# 03_USB.net
KiCad netlist of a schematic drawn in Altium Designer
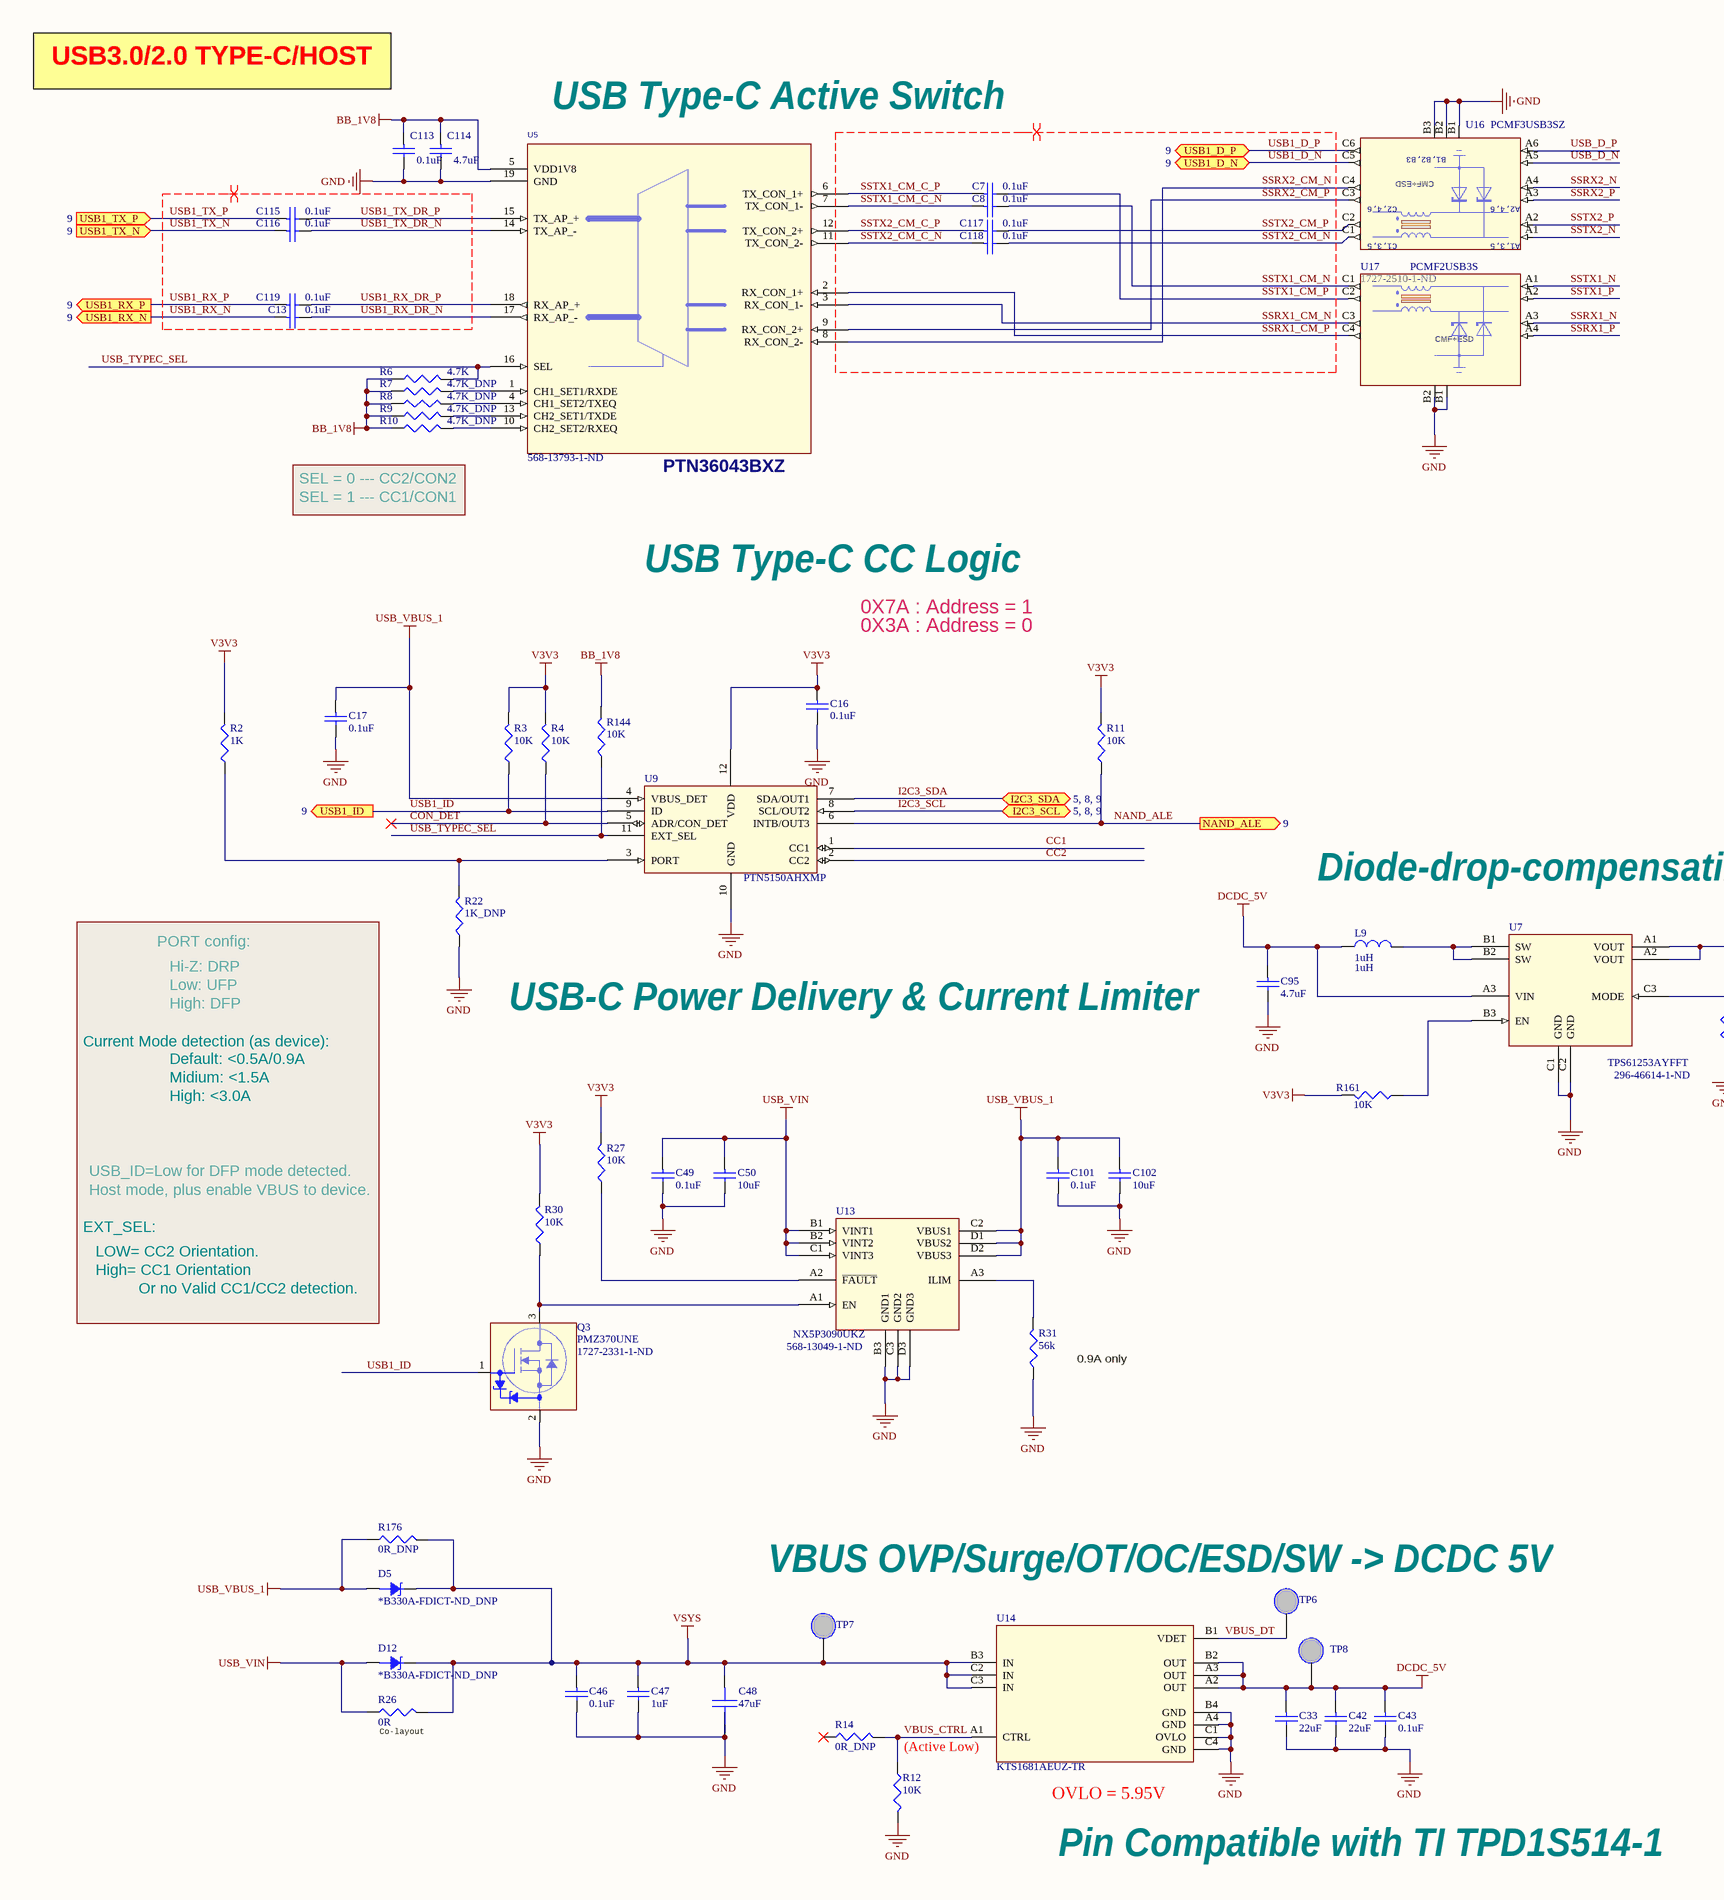
[diagram p0: 03_USB.SchDoc, left]
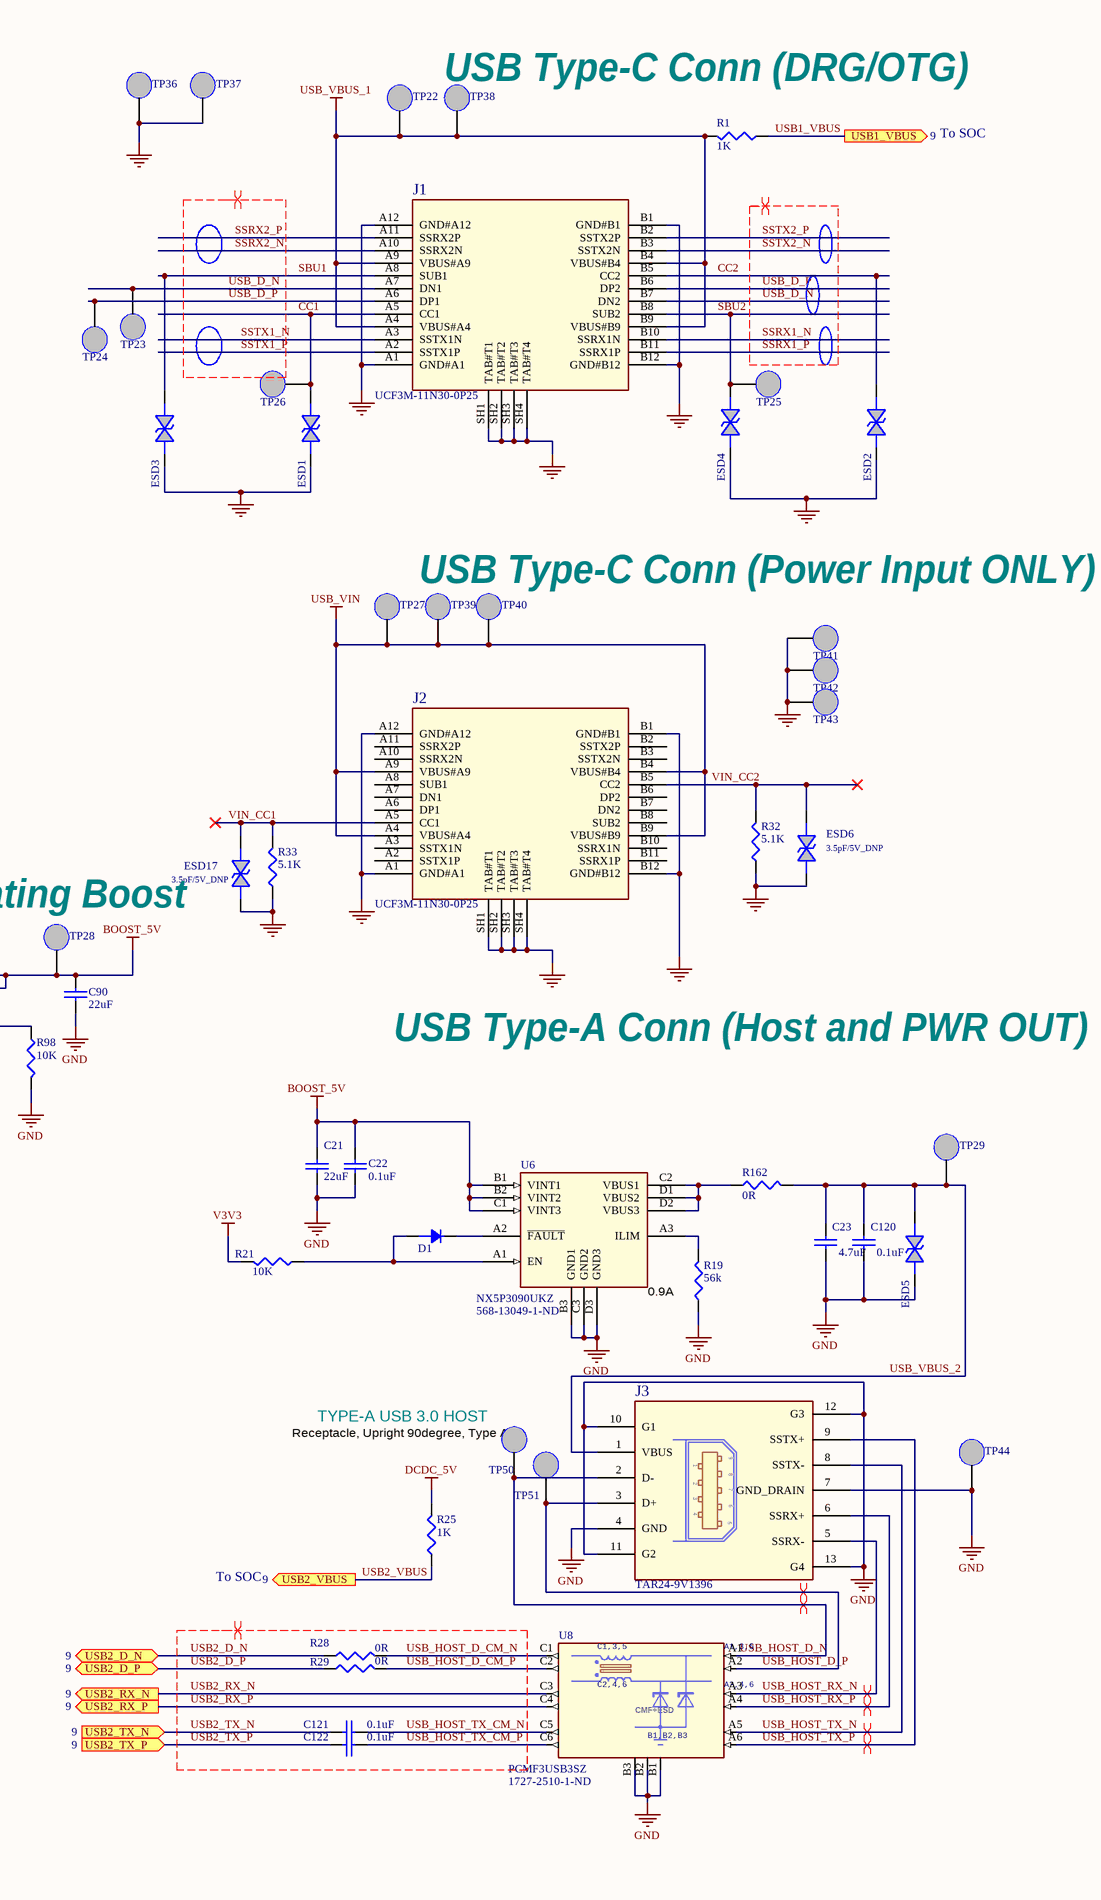
[diagram p1: 03_USB.SchDoc, right]

(export (version "E")
  (design (tool "Eeschema 10.0.6"))
  (components
    (comp (ref "C7")
      (value "0.1uF")
      (footprint "0201")
      (description "CAP CER 0.1UF 10V 10% X5R 0201")
      (fields (field (name "MPN") "C0603X5R1A104K030BC") (field (name "Comment") "0.1uF/10V"))
      (libsource (lib "links") (part "CAP_0201_0.1uF"))
    )
    (comp (ref "C8")
      (value "0.1uF")
      (footprint "0201")
      (description "CAP CER 0.1UF 10V 10% X5R 0201")
      (fields (field (name "MPN") "C0603X5R1A104K030BC") (field (name "Comment") "0.1uF/10V"))
      (libsource (lib "links") (part "CAP_0201_0.1uF"))
    )
    (comp (ref "C13")
      (value "0.1uF")
      (footprint "0201")
      (description "CAP CER 0.1UF 10V 10% X5R 0201")
      (fields (field (name "MPN") "C0603X5R1A104K030BC") (field (name "Comment") "0.1uF/10V"))
      (libsource (lib "links") (part "CAP_0201_0.1uF"))
    )
    (comp (ref "C16")
      (value "0.1uF")
      (footprint "0402")
      (description "CAP CER 0.1uF 25V 10% X7R 0402")
      (fields (field (name "MPN") "TMK105BJ104KV-F") (field (name "Comment") "0.1uF/25V"))
      (libsource (lib "links") (part "CAP_0402_0.1uF_25V"))
    )
    (comp (ref "C17")
      (value "0.1uF")
      (footprint "0402")
      (description "CAP CER 0.1uF 25V 10% X7R 0402")
      (fields (field (name "MPN") "TMK105BJ104KV-F") (field (name "Comment") "0.1uF/25V"))
      (libsource (lib "links") (part "CAP_0402_0.1uF_25V"))
    )
    (comp (ref "C21")
      (value "22uF")
      (footprint "0603")
      (description "CAP CER 22UF 6.3V 10% X5R 0603")
      (fields (field (name "MPN") "CL10A226KQ8NRNE") (field (name "Comment") "22uF/10V"))
      (libsource (lib "links") (part "CAP_0603_22uF"))
    )
    (comp (ref "C22")
      (value "0.1uF")
      (footprint "0201")
      (description "CAP CER 0.1UF 10V 10% X5R 0201")
      (fields (field (name "MPN") "C0603X5R1A104K030BC") (field (name "Comment") "0.1uF/10V"))
      (libsource (lib "links") (part "CAP_0201_0.1uF"))
    )
    (comp (ref "C23")
      (value "4.7uF")
      (footprint "0603")
      (description "CAP CER 4.7uF 10V 10% X5R 0603")
      (fields (field (name "MPN") "CGB3B1X5R1A475K055AC") (field (name "Comment") "4.7uF/10V"))
      (libsource (lib "links") (part "CAP_0603_4.7uF"))
    )
    (comp (ref "C33")
      (value "22uF")
      (footprint "0603")
      (description "CAP CER 22UF 6.3V 10% X5R 0603")
      (fields (field (name "MPN") "CL10A226KQ8NRNE") (field (name "Comment") "22uF/10V"))
      (libsource (lib "links") (part "CAP_0603_22uF"))
    )
    (comp (ref "C42")
      (value "22uF")
      (footprint "0603")
      (description "CAP CER 22UF 6.3V 10% X5R 0603")
      (fields (field (name "MPN") "CL10A226KQ8NRNE") (field (name "Comment") "22uF/10V"))
      (libsource (lib "links") (part "CAP_0603_22uF"))
    )
    (comp (ref "C43")
      (value "0.1uF")
      (footprint "0201")
      (description "CAP CER 0.1UF 10V 10% X5R 0201")
      (fields (field (name "MPN") "C0603X5R1A104K030BC") (field (name "Comment") "0.1uF/10V"))
      (libsource (lib "links") (part "CAP_0201_0.1uF"))
    )
    (comp (ref "C46")
      (value "0.1uF")
      (footprint "0402")
      (description "CAP CER 0.1uF 25V 10% X7R 0402")
      (fields (field (name "MPN") "TMK105BJ104KV-F") (field (name "Comment") "0.1uF/25V"))
      (libsource (lib "links") (part "CAP_0402_0.1uF_25V"))
    )
    (comp (ref "C47")
      (value "1uF")
      (footprint "0402")
      (description "CAP CER 1.0UF 25V 10% X5R 0402")
      (fields (field (name "MPN") "TMK105BJ105MV-F") (field (name "Comment") "1uF/25V"))
      (libsource (lib "links") (part "CAP_0402_1.0uF_25V"))
    )
    (comp (ref "C48")
      (value "47uF")
      (footprint "1206")
      (description "CAP CER 47UF 25V 20% 1206")
      (fields (field (name "MPN") "C3216JB1E476M160AC") (field (name "Comment") "47uF/25V"))
      (libsource (lib "links") (part "CAP_1206_47uF_25V"))
    )
    (comp (ref "C49")
      (value "0.1uF")
      (footprint "0402")
      (description "CAP CER 0.1uF 25V 10% X7R 0402")
      (fields (field (name "MPN") "TMK105BJ104KV-F") (field (name "Comment") "0.1uF/25V"))
      (libsource (lib "links") (part "CAP_0402_0.1uF_25V"))
    )
    (comp (ref "C50")
      (value "10uF")
      (footprint "0402")
      (description "CAP CER 10UF 10V 20% X5R 0402")
      (fields (field (name "MPN") "CL05A106MP5NUNC") (field (name "Comment") "10uF/10V"))
      (libsource (lib "links") (part "CAP_0603_4.7uF_35V"))
    )
    (comp (ref "C90")
      (value "22uF")
      (footprint "0603")
      (description "CAP CER 22UF 6.3V 10% X5R 0603")
      (fields (field (name "MPN") "CL10A226KQ8NRNE") (field (name "Comment") "10uF/10V"))
      (libsource (lib "links") (part "CAP_0603_22uF"))
    )
    (comp (ref "C95")
      (value "4.7uF")
      (footprint "0603")
      (description "CAP CER 4.7uF 10V 10% X5R 0603")
      (fields (field (name "MPN") "CGB3B1X5R1A475K055AC") (field (name "Comment") "4.7uF/10V"))
      (libsource (lib "links") (part "CAP_0603_4.7uF"))
    )
    (comp (ref "C101")
      (value "0.1uF")
      (footprint "0402")
      (description "CAP CER 0.1uF 25V 10% X7R 0402")
      (fields (field (name "MPN") "TMK105BJ104KV-F") (field (name "Comment") "0.1uF/25V"))
      (libsource (lib "links") (part "CAP_0402_0.1uF_25V"))
    )
    (comp (ref "C102")
      (value "10uF")
      (footprint "0402")
      (description "CAP CER 10UF 10V 20% X5R 0402")
      (fields (field (name "MPN") "CL05A106MP5NUNC") (field (name "Comment") "10uF/10V"))
      (libsource (lib "links") (part "CAP_0603_4.7uF_35V"))
    )
    (comp (ref "C113")
      (value "0.1uF")
      (footprint "0201")
      (description "CAP CER 0.1UF 10V 10% X5R 0201")
      (fields (field (name "MPN") "C0603X5R1A104K030BC") (field (name "Comment") "0.1uF/10V"))
      (libsource (lib "links") (part "CAP_0201_0.1uF"))
    )
    (comp (ref "C114")
      (value "4.7uF")
      (footprint "0402")
      (description "CAP CER 4.7UF 10V 20% X5R 0402")
      (fields (field (name "MPN") "C1005X5R1A475M050BC") (field (name "Comment") "4.7uF/10V"))
      (libsource (lib "links") (part "CAP_0402_4.7uF"))
    )
    (comp (ref "C115")
      (value "0.1uF")
      (footprint "0201")
      (description "CAP CER 0.1UF 10V 10% X5R 0201")
      (fields (field (name "MPN") "C0603X5R1A104K030BC") (field (name "Comment") "0.1uF/10V"))
      (libsource (lib "links") (part "CAP_0201_0.1uF"))
    )
    (comp (ref "C116")
      (value "0.1uF")
      (footprint "0201")
      (description "CAP CER 0.1UF 10V 10% X5R 0201")
      (fields (field (name "MPN") "C0603X5R1A104K030BC") (field (name "Comment") "0.1uF/10V"))
      (libsource (lib "links") (part "CAP_0201_0.1uF"))
    )
    (comp (ref "C117")
      (value "0.1uF")
      (footprint "0201")
      (description "CAP CER 0.1UF 10V 10% X5R 0201")
      (fields (field (name "MPN") "C0603X5R1A104K030BC") (field (name "Comment") "0.1uF/10V"))
      (libsource (lib "links") (part "CAP_0201_0.1uF"))
    )
    (comp (ref "C118")
      (value "0.1uF")
      (footprint "0201")
      (description "CAP CER 0.1UF 10V 10% X5R 0201")
      (fields (field (name "MPN") "C0603X5R1A104K030BC") (field (name "Comment") "0.1uF/10V"))
      (libsource (lib "links") (part "CAP_0201_0.1uF"))
    )
    (comp (ref "C119")
      (value "0.1uF")
      (footprint "0201")
      (description "CAP CER 0.1UF 10V 10% X5R 0201")
      (fields (field (name "MPN") "C0603X5R1A104K030BC") (field (name "Comment") "0.1uF/10V"))
      (libsource (lib "links") (part "CAP_0201_0.1uF"))
    )
    (comp (ref "C120")
      (value "0.1uF")
      (footprint "0201")
      (description "CAP CER 0.1UF 10V 10% X5R 0201")
      (fields (field (name "MPN") "C0603X5R1A104K030BC") (field (name "Comment") "0.1uF/10V"))
      (libsource (lib "links") (part "CAP_0201_0.1uF"))
    )
    (comp (ref "C121")
      (value "0.1uF")
      (footprint "0201")
      (description "CAP CER 0.1UF 10V 10% X5R 0201")
      (fields (field (name "MPN") "C0603X5R1A104K030BC") (field (name "Comment") "0.1uF/10V"))
      (libsource (lib "links") (part "CAP_0201_0.1uF"))
    )
    (comp (ref "C122")
      (value "0.1uF")
      (footprint "0201")
      (description "CAP CER 0.1UF 10V 10% X5R 0201")
      (fields (field (name "MPN") "C0603X5R1A104K030BC") (field (name "Comment") "0.1uF/10V"))
      (libsource (lib "links") (part "CAP_0201_0.1uF"))
    )
    (comp (ref "D1")
      (value "CUS10F30")
      (footprint "0805-Diode")
      (description "DIODE SCHOTTKY 20V 1A 0805")
      (libsource (lib "SpacePark") (part "Diode_Schottky_0805"))
    )
    (comp (ref "D5")
      (value "B330A-FDICT-ND_DNP")
      (footprint "SMA-Diode")
      (description "Diode_Schottky_B330A-13-F")
      (fields
        (field (name "SUPPLIER PART NUMBER 1") "*B330A-FDICT-ND_DNP")
        (field (name "MPN") "B330A-FDICT-ND")
      )
      (libsource (lib "SpacePark") (part "B330A-FDICT-ND_DNP"))
    )
    (comp (ref "D12")
      (value "B330A-FDICT-ND_DNP")
      (footprint "SMA-Diode")
      (description "Diode_Schottky_B330A-13-F")
      (fields
        (field (name "SUPPLIER PART NUMBER 1") "*B330A-FDICT-ND_DNP")
        (field (name "MPN") "B330A-FDICT-ND")
      )
      (libsource (lib "SpacePark") (part "B330A-FDICT-ND_DNP"))
    )
    (comp (ref "ESD1")
      (value "3.5pF/5V")
      (footprint "0201")
      (description "DIODE TVS 15kV 10V 50A 8pF SMT RoHS")
      (fields (field (name "MPN") "DESD5V0V1BCSP-7"))
      (libsource (lib "links") (part "DIODE BI-DIR TRIG"))
    )
    (comp (ref "ESD2")
      (value "3.5pF/5V")
      (footprint "0201")
      (description "DIODE TVS 15kV 10V 50A 8pF SMT RoHS")
      (fields (field (name "MPN") "DESD5V0V1BCSP-7"))
      (libsource (lib "links") (part "DIODE BI-DIR TRIG"))
    )
    (comp (ref "ESD3")
      (value "3.5pF/5V")
      (footprint "0201")
      (description "DIODE TVS 15kV 10V 50A 8pF SMT RoHS")
      (fields (field (name "MPN") "DESD5V0V1BCSP-7"))
      (libsource (lib "links") (part "DIODE BI-DIR TRIG"))
    )
    (comp (ref "ESD4")
      (value "3.5pF/5V")
      (footprint "0201")
      (description "DIODE TVS 15kV 10V 50A 8pF SMT RoHS")
      (fields (field (name "MPN") "DESD5V0V1BCSP-7"))
      (libsource (lib "links") (part "DIODE BI-DIR TRIG"))
    )
    (comp (ref "ESD5")
      (value "3.5pF/5V")
      (footprint "0201")
      (description "DIODE TVS 15kV 10V 50A 8pF SMT RoHS")
      (fields (field (name "MPN") "DESD5V0V1BCSP-7"))
      (libsource (lib "links") (part "DIODE BI-DIR TRIG"))
    )
    (comp (ref "ESD6")
      (value "3.5pF/5V_DNP")
      (footprint "0201")
      (description "DIODE TVS 15kV 10V 50A 8pF SMT RoHS")
      (fields (field (name "MPN") "DESD5V0V1BCSP-7"))
      (libsource (lib "links") (part "DIODE BI-DIR TRIG"))
    )
    (comp (ref "ESD17")
      (value "3.5pF/5V_DNP")
      (footprint "0201")
      (description "DIODE TVS 15kV 10V 50A 8pF SMT RoHS")
      (fields (field (name "MPN") "DESD5V0V1BCSP-7"))
      (libsource (lib "links") (part "DIODE BI-DIR TRIG"))
    )
    (comp (ref "J1")
      (value "UCF3M-11N30-0P25")
      (footprint "USB12_0_5-UCF3M-11N30-0P25")
      (libsource (lib "SpacePark") (part "CONN_USBC_RCPT_UCF3M-11N30-0P25"))
    )
    (comp (ref "J2")
      (value "UCF3M-11N30-0P25")
      (footprint "USB12_0_5-UCF3M-11N30-0P25")
      (libsource (lib "SpacePark") (part "CONN_USBC_RCPT_UCF3M-11N30-0P25"))
    )
    (comp (ref "J3")
      (value "TAR24-9V1396")
      (footprint "USB9-3_0-TAR24-9V1396")
      (description "CONN, USB TYPE A, 3.0 REC TH")
      (libsource (lib "SpacePark") (part "CONN_USBA_ACON_TAR24-9V1396"))
    )
    (comp (ref "L9")
      (value "1uH")
      (footprint "INDC2016X12L")
      (description "FIXED IND 1UH 2.7A 72 MOHM SMD")
      (fields (field (name "ALTIUM_VALUE") "1uH") (field (name "MPN") "VLS201612HBX-1R0M-1"))
      (libsource (lib "links") (part "INDUCTOR_VLS201612HBX-1R0M-1"))
    )
    (comp (ref "Q3")
      (value "PMZ370UNE")
      (footprint "DFN10106B")
      (description "N-Channel 30V 590mA, SMT DFN1006B-3")
      (fields (field (name "SUPPLIER PART NUMBER 1") "1727-2331-1-ND") (field (name "MPN") "PMZB550UNEYL"))
      (libsource (lib "SpacePark") (part "NMOS_NX3008NBK"))
    )
    (comp (ref "R1")
      (value "1K")
      (footprint "0201")
      (description "RES SMD 1K OHM 1% 1/20W 0201")
      (fields (field (name "MPN") "ERJ-1GEF1001C") (field (name "Comment") "1K/1%"))
      (libsource (lib "links") (part "R_0201_1K"))
    )
    (comp (ref "R2")
      (value "1K")
      (footprint "0201")
      (description "RES SMD 1K OHM 1% 1/20W 0201")
      (fields (field (name "MPN") "ERJ-1GEF1001C") (field (name "Comment") "1K/1%"))
      (libsource (lib "links") (part "R_0201_1K"))
    )
    (comp (ref "R3")
      (value "10K")
      (footprint "0201")
      (description "RES SMD 10K OHM JUMPER 1/20W  0201")
      (fields (field (name "MPN") "ERJ-1GEF103C"))
      (libsource (lib "links") (part "R_0201_10K"))
    )
    (comp (ref "R4")
      (value "10K")
      (footprint "0201")
      (description "RES SMD 10K OHM JUMPER 1/20W  0201")
      (fields (field (name "MPN") "ERJ-1GEF103C"))
      (libsource (lib "links") (part "R_0201_10K"))
    )
    (comp (ref "R6")
      (value "4.7K")
      (footprint "0201")
      (description "RES SMD 4.7K OHM 1% 1/20W 0201")
      (fields (field (name "MPN") "ERJ-1GEF4701C"))
      (libsource (lib "links") (part "R_0201_4.7K"))
    )
    (comp (ref "R7")
      (value "4.7K_DNP")
      (footprint "0201")
      (description "RES SMD 4.7K OHM 1% 1/20W 0201")
      (fields (field (name "MPN") "ERJ-1GEF4701C") (field (name "Comment") "4.7K"))
      (libsource (lib "links") (part "R_0201_4.7K"))
    )
    (comp (ref "R8")
      (value "4.7K_DNP")
      (footprint "0201")
      (description "RES SMD 4.7K OHM 1% 1/20W 0201")
      (fields (field (name "MPN") "ERJ-1GEF4701C") (field (name "Comment") "4.7K"))
      (libsource (lib "links") (part "R_0201_4.7K"))
    )
    (comp (ref "R9")
      (value "4.7K_DNP")
      (footprint "0201")
      (description "RES SMD 4.7K OHM 1% 1/20W 0201")
      (fields (field (name "MPN") "ERJ-1GEF4701C") (field (name "Comment") "4.7K"))
      (libsource (lib "links") (part "R_0201_4.7K"))
    )
    (comp (ref "R10")
      (value "4.7K_DNP")
      (footprint "0201")
      (description "RES SMD 4.7K OHM 1% 1/20W 0201")
      (fields (field (name "MPN") "ERJ-1GEF4701C") (field (name "Comment") "4.7K"))
      (libsource (lib "links") (part "R_0201_4.7K"))
    )
    (comp (ref "R11")
      (value "10K")
      (footprint "0201")
      (description "RES SMD 10K OHM JUMPER 1/20W  0201")
      (fields (field (name "MPN") "ERJ-1GEF103C"))
      (libsource (lib "links") (part "R_0201_10K"))
    )
    (comp (ref "R12")
      (value "10K")
      (footprint "0201")
      (description "RES SMD 10K OHM JUMPER 1/20W  0201")
      (fields (field (name "MPN") "ERJ-1GEF103C"))
      (libsource (lib "links") (part "R_0201_10K"))
    )
    (comp (ref "R14")
      (value "0R_DNP")
      (footprint "0201")
      (description "RES SMD 0.0OHM JUMPER 1/20W 0201")
      (fields (field (name "MPN") "ERJ-1GN0R00C"))
      (libsource (lib "links") (part "R_0201_0"))
    )
    (comp (ref "R19")
      (value "56k")
      (footprint "0402")
      (description "RES SMD 56K OHM 1% 1/10W 0402")
      (fields (field (name "MPN") "ERJ-2RKF5602X"))
      (libsource (lib "links") (part "R_0402_56k"))
    )
    (comp (ref "R21")
      (value "10K")
      (footprint "0201")
      (description "RES SMD 10K OHM JUMPER 1/20W  0201")
      (fields (field (name "MPN") "ERJ-1GEF103C"))
      (libsource (lib "links") (part "R_0201_10K"))
    )
    (comp (ref "R22")
      (value "1K_DNP")
      (footprint "0201")
      (description "RES SMD 1K OHM 1% 1/20W 0201")
      (fields (field (name "MPN") "ERJ-1GEF1001C"))
      (libsource (lib "links") (part "R_0201_1K"))
    )
    (comp (ref "R25")
      (value "1K")
      (footprint "0201")
      (description "RES SMD 1K OHM 1% 1/20W 0201")
      (fields (field (name "MPN") "ERJ-1GEF1001C") (field (name "Comment") "1K/1%"))
      (libsource (lib "links") (part "R_0201_1K"))
    )
    (comp (ref "R26")
      (value "0R")
      (footprint "1206")
      (description "RES SMD 0.0 OHM JUMPER 1/4W 1206")
      (fields (field (name "MPN") "RC1206JR-070RL"))
      (libsource (lib "links") (part "R_1206_0"))
    )
    (comp (ref "R27")
      (value "10K")
      (footprint "0201")
      (description "RES SMD 10K OHM JUMPER 1/20W  0201")
      (fields (field (name "MPN") "ERJ-1GEF103C"))
      (libsource (lib "links") (part "R_0201_10K"))
    )
    (comp (ref "R28")
      (value "0R")
      (footprint "0201")
      (description "RES SMD 0.0OHM JUMPER 1/20W 0201")
      (fields (field (name "MPN") "ERJ-1GN0R00C"))
      (libsource (lib "links") (part "R_0201_0"))
    )
    (comp (ref "R29")
      (value "0R")
      (footprint "0201")
      (description "RES SMD 0.0OHM JUMPER 1/20W 0201")
      (fields (field (name "MPN") "ERJ-1GN0R00C"))
      (libsource (lib "links") (part "R_0201_0"))
    )
    (comp (ref "R30")
      (value "10K")
      (footprint "0201")
      (description "RES SMD 10K OHM JUMPER 1/20W  0201")
      (fields (field (name "MPN") "ERJ-1GEF103C"))
      (libsource (lib "links") (part "R_0201_10K"))
    )
    (comp (ref "R31")
      (value "56k")
      (footprint "0402")
      (description "RES SMD 56K OHM 1% 1/10W 0402")
      (fields (field (name "MPN") "ERJ-2RKF5602X"))
      (libsource (lib "links") (part "R_0402_56k"))
    )
    (comp (ref "R32")
      (value "5.1K")
      (footprint "0201")
      (description "RES SMD 5.1K OHM JUMPER 1/20W  0201")
      (fields (field (name "MPN") "ERJ-JGEF5101C"))
      (libsource (lib "links") (part "R_0201_5.1K"))
    )
    (comp (ref "R33")
      (value "5.1K")
      (footprint "0201")
      (description "RES SMD 5.1K OHM JUMPER 1/20W  0201")
      (fields (field (name "MPN") "ERJ-JGEF5101C"))
      (libsource (lib "links") (part "R_0201_5.1K"))
    )
    (comp (ref "R98")
      (value "10K")
      (footprint "0201")
      (description "RES SMD 10K OHM JUMPER 1/20W  0201")
      (fields (field (name "MPN") "ERJ-1GEF103C"))
      (libsource (lib "links") (part "R_0201_10K"))
    )
    (comp (ref "R144")
      (value "10K")
      (footprint "0201")
      (description "RES SMD 10K OHM JUMPER 1/20W  0201")
      (fields (field (name "MPN") "ERJ-1GEF103C"))
      (libsource (lib "links") (part "R_0201_10K"))
    )
    (comp (ref "R161")
      (value "10K")
      (footprint "0201")
      (description "RES SMD 10K OHM JUMPER 1/20W  0201")
      (fields (field (name "MPN") "ERJ-1GEF103C"))
      (libsource (lib "links") (part "R_0201_10K"))
    )
    (comp (ref "R162")
      (value "0R")
      (footprint "0402")
      (description "RES SMD 0.0 OHM JUMPER 1/10W  0402")
      (fields (field (name "MPN") "ERJ-2GE0R00X"))
      (libsource (lib "links") (part "R_0402_0"))
    )
    (comp (ref "R176")
      (value "0R_DNP")
      (footprint "1206")
      (description "RES SMD 0.0 OHM JUMPER 1/4W 1206")
      (fields (field (name "MPN") "RC1206JR-070RL") (field (name "Comment") "0R"))
      (libsource (lib "links") (part "R_1206_0"))
    )
    (comp (ref "TP6")
      (value "TP NM")
      (footprint "TP_SMD_L")
      (description "TEST POINT (Large)")
      (libsource (lib "links") (part "TP_L"))
    )
    (comp (ref "TP7")
      (value "TP NM")
      (footprint "TP_SMD_L")
      (description "TEST POINT (Large)")
      (libsource (lib "links") (part "TP_L"))
    )
    (comp (ref "TP8")
      (value "TP NM")
      (footprint "TP_SMD_L")
      (description "TEST POINT (Large)")
      (libsource (lib "links") (part "TP_L"))
    )
    (comp (ref "TP22")
      (value "TP NM")
      (footprint "TP_SMD_L")
      (description "TEST POINT (Large)")
      (libsource (lib "links") (part "TP_L"))
    )
    (comp (ref "TP23")
      (value "TP NM")
      (footprint "TP_SMD")
      (description "TEST POIN")
      (libsource (lib "links") (part "TP"))
    )
    (comp (ref "TP24")
      (value "TP NM")
      (footprint "TP_SMD")
      (description "TEST POIN")
      (libsource (lib "links") (part "TP"))
    )
    (comp (ref "TP25")
      (value "TP NM")
      (footprint "TP_SMD")
      (description "TEST POIN")
      (libsource (lib "links") (part "TP"))
    )
    (comp (ref "TP26")
      (value "TP NM")
      (footprint "TP_SMD")
      (description "TEST POIN")
      (libsource (lib "links") (part "TP"))
    )
    (comp (ref "TP27")
      (value "TP NM")
      (footprint "TP_SMD_L")
      (description "TEST POINT (Large)")
      (libsource (lib "links") (part "TP_L"))
    )
    (comp (ref "TP28")
      (value "TP NM")
      (footprint "TP_SMD_L")
      (description "TEST POINT (Large)")
      (libsource (lib "links") (part "TP_L"))
    )
    (comp (ref "TP29")
      (value "TP NM")
      (footprint "TP_SMD_L")
      (description "TEST POINT (Large)")
      (libsource (lib "links") (part "TP_L"))
    )
    (comp (ref "TP36")
      (value "TP NM")
      (footprint "TP_SMD_L")
      (description "TEST POINT (Large)")
      (libsource (lib "links") (part "TP_L"))
    )
    (comp (ref "TP37")
      (value "TP NM")
      (footprint "TP_SMD_L")
      (description "TEST POINT (Large)")
      (libsource (lib "links") (part "TP_L"))
    )
    (comp (ref "TP38")
      (value "TP NM")
      (footprint "TP_SMD_L")
      (description "TEST POINT (Large)")
      (libsource (lib "links") (part "TP_L"))
    )
    (comp (ref "TP39")
      (value "TP NM")
      (footprint "TP_SMD_L")
      (description "TEST POINT (Large)")
      (libsource (lib "links") (part "TP_L"))
    )
    (comp (ref "TP40")
      (value "TP NM")
      (footprint "TP_SMD_L")
      (description "TEST POINT (Large)")
      (libsource (lib "links") (part "TP_L"))
    )
    (comp (ref "TP41")
      (value "TP NM")
      (footprint "TP_SMD_L")
      (description "TEST POINT (Large)")
      (libsource (lib "links") (part "TP_L"))
    )
    (comp (ref "TP42")
      (value "TP NM")
      (footprint "TP_SMD_L")
      (description "TEST POINT (Large)")
      (libsource (lib "links") (part "TP_L"))
    )
    (comp (ref "TP43")
      (value "TP NM")
      (footprint "TP_SMD_L")
      (description "TEST POINT (Large)")
      (libsource (lib "links") (part "TP_L"))
    )
    (comp (ref "TP44")
      (value "TP NM")
      (footprint "TP_SMD_L")
      (description "TEST POINT (Large)")
      (libsource (lib "links") (part "TP_L"))
    )
    (comp (ref "TP50")
      (value "TP NM")
      (footprint "TP_SMD_L")
      (description "TEST POINT (Large)")
      (libsource (lib "links") (part "TP_L"))
    )
    (comp (ref "TP51")
      (value "TP NM")
      (footprint "TP_SMD_L")
      (description "TEST POINT (Large)")
      (libsource (lib "links") (part "TP_L"))
    )
    (comp (ref "U5")
      (value "PTN36043BXZ")
      (footprint "DHXQFN18_0P4_2X2P45")
      (description "IC USB TYPE-C SS ACTIVE DEMUX 1.8V DHXQFN18")
      (fields (field (name "SUPPLIER PART NUMBER 1") "568-13793-1-ND"))
      (libsource (lib "SpacePark") (part "PTN36043BX_DHXQFN18_23"))
    )
    (comp (ref "U6")
      (value "NX5P3090UKZ")
      (footprint "WLCSP12_0P4_1P38X1P68MM_SMDP")
      (fields (field (name "SUPPLIER PART NUMBER 1") "568-13049-1-ND"))
      (libsource (lib "SpacePark") (part "NX5P3090UKZ_WLCSP12"))
    )
    (comp (ref "U7")
      (value "TPS61253AYFFT")
      (footprint "WLCSP_BGA3x3")
      (fields (field (name "SUPPLIER PART NUMBER 1") "296-46614-1-ND"))
      (libsource (lib "SpacePark") (part "TPS61253A"))
    )
    (comp (ref "U8")
      (value "PCMF3USB3SZ")
      (footprint "WLCSP15_0P4_2P42X1P22_SMDP")
      (fields (field (name "SUPPLIER PART NUMBER 1") "1727-2510-1-ND"))
      (libsource (lib "SpacePark") (part "PCMF3USB3S_A"))
    )
    (comp (ref "U9")
      (value "PTN5150AHXMP")
      (footprint "X2QFN12_0P4_1P6X1P6")
      (libsource (lib "SpacePark") (part "PTN5150A_X2QFN12"))
    )
    (comp (ref "U13")
      (value "NX5P3090UKZ")
      (footprint "WLCSP12_0P4_1P38X1P68MM_SMDP")
      (fields (field (name "SUPPLIER PART NUMBER 1") "568-13049-1-ND"))
      (libsource (lib "SpacePark") (part "NX5P3090UKZ_WLCSP12"))
    )
    (comp (ref "U14")
      (value "KTS1681AEUZ-TR")
      (footprint "WLCSP_BGA3x4")
      (description "USB Over Voltage, SUrge and ESD protection for VBUS, WCSP12")
      (libsource (lib "SpacePark") (part "KTS1681A"))
    )
    (comp (ref "U16")
      (value "PCMF3USB3SZ")
      (footprint "WLCSP15_0P4_2P42X1P22_SMDP")
      (fields (field (name "SUPPLIER PART NUMBER 1") "1727-2510-1-ND"))
      (libsource (lib "") (part "PCMF3USB3S_A_1"))
    )
    (comp (ref "U17")
      (value "PCMF2USB3S")
      (footprint "WLCSP10_0P4_1P2X1P6MM_SMDP")
      (libsource (lib "SpacePark") (part "PCMF2USB3S_10P"))
    )
  )
  (nets
    (net (code "1") (name "/CC1") (class "Default")
      (node (ref "ESD1") (pin "2") (pinfunction "2_2") (pintype "passive"))
      (node (ref "J1") (pin "A5") (pinfunction "CC1_A5") (pintype "passive"))
      (node (ref "TP26") (pin "1") (pinfunction "1_1") (pintype "passive"))
      (node (ref "U9") (pin "1") (pinfunction "CC1_1") (pintype "bidirectional"))
    )
    (net (code "2") (name "/CC2") (class "Default")
      (node (ref "ESD2") (pin "2") (pinfunction "2_2") (pintype "passive"))
      (node (ref "J1") (pin "B5") (pinfunction "CC2_B5") (pintype "passive"))
      (node (ref "U9") (pin "2") (pinfunction "CC2_2") (pintype "bidirectional"))
    )
    (net (code "3") (name "/CON_DET") (class "Default")
      (node (ref "R4") (pin "1") (pintype "passive"))
      (node (ref "U9") (pin "5") (pinfunction "ADR/CON_DET_5") (pintype "bidirectional"))
    )
    (net (code "4") (name "/I2C3_SCL") (class "Default")
      (node (ref "U9") (pin "8") (pinfunction "SCL/OUT2_8") (pintype "input"))
    )
    (net (code "5") (name "/I2C3_SDA") (class "Default")
      (node (ref "U9") (pin "7") (pinfunction "SDA/OUT1_7") (pintype "open_collector"))
    )
    (net (code "6") (name "/NAND_ALE") (class "Default")
      (node (ref "R11") (pin "1") (pintype "passive"))
      (node (ref "U9") (pin "6") (pinfunction "INTB/OUT3_6") (pintype "open_collector"))
    )
    (net (code "7") (name "/SBU1") (class "Default")
      (node (ref "ESD3") (pin "2") (pinfunction "2_2") (pintype "passive"))
      (node (ref "J1") (pin "A8") (pinfunction "SUB1_A8") (pintype "passive"))
    )
    (net (code "8") (name "/SBU2") (class "Default")
      (node (ref "ESD4") (pin "2") (pinfunction "2_2") (pintype "passive"))
      (node (ref "J1") (pin "B8") (pinfunction "SUB2_B8") (pintype "passive"))
      (node (ref "TP25") (pin "1") (pinfunction "1_1") (pintype "passive"))
    )
    (net (code "9") (name "/SSRX1_CM_N") (class "Default")
      (node (ref "U17") (pin "C3") (pinfunction "CH2_OUT+_C3") (pintype "output"))
      (node (ref "U5") (pin "3") (pinfunction "RX_CON_1-_3") (pintype "input"))
    )
    (net (code "10") (name "/SSRX1_CM_P") (class "Default")
      (node (ref "U17") (pin "C4") (pinfunction "CH2_OUT-_C4") (pintype "output"))
      (node (ref "U5") (pin "2") (pinfunction "RX_CON_1+_2") (pintype "input"))
    )
    (net (code "11") (name "/SSRX1_N") (class "Default")
      (node (ref "J1") (pin "B10") (pinfunction "SSRX1N_B10") (pintype "passive"))
      (node (ref "U17") (pin "A3") (pinfunction "CH2_IN+_A3") (pintype "input"))
    )
    (net (code "12") (name "/SSRX1_P") (class "Default")
      (node (ref "J1") (pin "B11") (pinfunction "SSRX1P_B11") (pintype "passive"))
      (node (ref "U17") (pin "A4") (pinfunction "CH2_IN-_A4") (pintype "input"))
    )
    (net (code "13") (name "/SSRX2_CM_N") (class "Default")
      (node (ref "U16") (pin "C4") (pinfunction "CH2_OUT-_C4") (pintype "output"))
      (node (ref "U5") (pin "8") (pinfunction "RX_CON_2-_8") (pintype "input"))
    )
    (net (code "14") (name "/SSRX2_CM_P") (class "Default")
      (node (ref "U16") (pin "C3") (pinfunction "CH2_OUT+_C3") (pintype "output"))
      (node (ref "U5") (pin "9") (pinfunction "RX_CON_2+_9") (pintype "input"))
    )
    (net (code "15") (name "/SSRX2_N") (class "Default")
      (node (ref "J1") (pin "A10") (pinfunction "SSRX2N_A10") (pintype "passive"))
      (node (ref "U16") (pin "A4") (pinfunction "CH2_IN-_A4") (pintype "input"))
    )
    (net (code "16") (name "/SSRX2_P") (class "Default")
      (node (ref "J1") (pin "A11") (pinfunction "SSRX2P_A11") (pintype "passive"))
      (node (ref "U16") (pin "A3") (pinfunction "CH2_IN+_A3") (pintype "input"))
    )
    (net (code "17") (name "/SSTX1_CM_C_N") (class "Default")
      (node (ref "C8") (pin "1") (pinfunction "1_1") (pintype "passive"))
      (node (ref "U5") (pin "7") (pinfunction "TX_CON_1-_7") (pintype "output"))
    )
    (net (code "18") (name "/SSTX1_CM_C_P") (class "Default")
      (node (ref "C7") (pin "1") (pinfunction "1_1") (pintype "passive"))
      (node (ref "U5") (pin "6") (pinfunction "TX_CON_1+_6") (pintype "output"))
    )
    (net (code "19") (name "/SSTX1_CM_N") (class "Default")
      (node (ref "C8") (pin "2") (pinfunction "2_2") (pintype "passive"))
      (node (ref "U17") (pin "C1") (pinfunction "CH1_OUT+_C1") (pintype "output"))
    )
    (net (code "20") (name "/SSTX1_CM_P") (class "Default")
      (node (ref "C7") (pin "2") (pinfunction "2_2") (pintype "passive"))
      (node (ref "U17") (pin "C2") (pinfunction "CH1_OUT-_C2") (pintype "output"))
    )
    (net (code "21") (name "/SSTX1_N") (class "Default")
      (node (ref "J1") (pin "A3") (pinfunction "SSTX1N_A3") (pintype "passive"))
      (node (ref "U17") (pin "A1") (pinfunction "CH1_IN+_A1") (pintype "input"))
    )
    (net (code "22") (name "/SSTX1_P") (class "Default")
      (node (ref "J1") (pin "A2") (pinfunction "SSTX1P_A2") (pintype "passive"))
      (node (ref "U17") (pin "A2") (pinfunction "CH1_IN-_A2") (pintype "input"))
    )
    (net (code "23") (name "/SSTX2_CM_C_N") (class "Default")
      (node (ref "C118") (pin "1") (pinfunction "1_1") (pintype "passive"))
      (node (ref "U5") (pin "11") (pinfunction "TX_CON_2-_11") (pintype "output"))
    )
    (net (code "24") (name "/SSTX2_CM_C_P") (class "Default")
      (node (ref "C117") (pin "1") (pinfunction "1_1") (pintype "passive"))
      (node (ref "U5") (pin "12") (pinfunction "TX_CON_2+_12") (pintype "output"))
    )
    (net (code "25") (name "/SSTX2_CM_N") (class "Default")
      (node (ref "C118") (pin "2") (pinfunction "2_2") (pintype "passive"))
      (node (ref "U16") (pin "C1") (pinfunction "CH1_OUT+_C1") (pintype "output"))
    )
    (net (code "26") (name "/SSTX2_CM_P") (class "Default")
      (node (ref "C117") (pin "2") (pinfunction "2_2") (pintype "passive"))
      (node (ref "U16") (pin "C2") (pinfunction "CH1_OUT-_C2") (pintype "output"))
    )
    (net (code "27") (name "/SSTX2_N") (class "Default")
      (node (ref "J1") (pin "B3") (pinfunction "SSTX2N_B3") (pintype "passive"))
      (node (ref "U16") (pin "A1") (pinfunction "CH1_IN+_A1") (pintype "input"))
    )
    (net (code "28") (name "/SSTX2_P") (class "Default")
      (node (ref "J1") (pin "B2") (pinfunction "SSTX2P_B2") (pintype "passive"))
      (node (ref "U16") (pin "A2") (pinfunction "CH1_IN-_A2") (pintype "input"))
    )
    (net (code "29") (name "/USB1_D_N") (class "Default")
      (node (ref "U16") (pin "C5") (pinfunction "CH3_OUT+_C5") (pintype "output"))
    )
    (net (code "30") (name "/USB1_D_P") (class "Default")
      (node (ref "U16") (pin "C6") (pinfunction "CH3_OUT-_C6") (pintype "output"))
    )
    (net (code "31") (name "/USB1_ID") (class "Default")
      (node (ref "Q3") (pin "1") (pinfunction "GATE_1") (pintype "passive"))
      (node (ref "R3") (pin "1") (pintype "passive"))
      (node (ref "U9") (pin "9") (pinfunction "ID_9") (pintype "open_collector"))
    )
    (net (code "32") (name "/USB1_RX_DR_N") (class "Default")
      (node (ref "C13") (pin "2") (pinfunction "2_2") (pintype "passive"))
      (node (ref "U5") (pin "17") (pinfunction "RX_AP_-_17") (pintype "output"))
    )
    (net (code "33") (name "/USB1_RX_DR_P") (class "Default")
      (node (ref "C119") (pin "2") (pinfunction "2_2") (pintype "passive"))
      (node (ref "U5") (pin "18") (pinfunction "RX_AP_+_18") (pintype "output"))
    )
    (net (code "34") (name "/USB1_RX_N") (class "Default")
      (node (ref "C13") (pin "1") (pinfunction "1_1") (pintype "passive"))
    )
    (net (code "35") (name "/USB1_RX_P") (class "Default")
      (node (ref "C119") (pin "1") (pinfunction "1_1") (pintype "passive"))
    )
    (net (code "36") (name "/USB1_TX_DR_N") (class "Default")
      (node (ref "C116") (pin "2") (pinfunction "2_2") (pintype "passive"))
      (node (ref "U5") (pin "14") (pinfunction "TX_AP_-_14") (pintype "input"))
    )
    (net (code "37") (name "/USB1_TX_DR_P") (class "Default")
      (node (ref "C115") (pin "2") (pinfunction "2_2") (pintype "passive"))
      (node (ref "U5") (pin "15") (pinfunction "TX_AP_+_15") (pintype "input"))
    )
    (net (code "38") (name "/USB1_TX_N") (class "Default")
      (node (ref "C116") (pin "1") (pinfunction "1_1") (pintype "passive"))
    )
    (net (code "39") (name "/USB1_TX_P") (class "Default")
      (node (ref "C115") (pin "1") (pinfunction "1_1") (pintype "passive"))
    )
    (net (code "40") (name "/USB1_VBUS") (class "Default") (node (ref "R1") (pin "1") (pintype "passive")))
    (net (code "41") (name "/USB2_D_N") (class "Default") (node (ref "R28") (pin "1") (pintype "passive")))
    (net (code "42") (name "/USB2_D_P") (class "Default") (node (ref "R29") (pin "1") (pintype "passive")))
    (net (code "43") (name "/USB2_RX_N") (class "Default")
      (node (ref "U8") (pin "C3") (pinfunction "CH2_OUT+_C3") (pintype "output"))
    )
    (net (code "44") (name "/USB2_RX_P") (class "Default")
      (node (ref "U8") (pin "C4") (pinfunction "CH2_OUT-_C4") (pintype "output"))
    )
    (net (code "45") (name "/USB2_TX_N") (class "Default")
      (node (ref "C121") (pin "1") (pinfunction "1_1") (pintype "passive"))
    )
    (net (code "46") (name "/USB2_TX_P") (class "Default")
      (node (ref "C122") (pin "1") (pinfunction "1_1") (pintype "passive"))
    )
    (net (code "47") (name "/USB2_VBUS") (class "Default") (node (ref "R25") (pin "1") (pintype "passive")))
    (net (code "48") (name "/USB_D_N") (class "Default")
      (node (ref "J1") (pin "A7") (pinfunction "DN1_A7") (pintype "passive"))
      (node (ref "J1") (pin "B7") (pinfunction "DN2_B7") (pintype "passive"))
      (node (ref "TP23") (pin "1") (pinfunction "1_1") (pintype "passive"))
      (node (ref "U16") (pin "A5") (pinfunction "CH3_IN+_A5") (pintype "input"))
    )
    (net (code "49") (name "/USB_D_P") (class "Default")
      (node (ref "J1") (pin "A6") (pinfunction "DP1_A6") (pintype "passive"))
      (node (ref "J1") (pin "B6") (pinfunction "DP2_B6") (pintype "passive"))
      (node (ref "TP24") (pin "1") (pinfunction "1_1") (pintype "passive"))
      (node (ref "U16") (pin "A6") (pinfunction "CH3_IN-_A6") (pintype "input"))
    )
    (net (code "50") (name "/USB_HOST_D_CM_N") (class "Default")
      (node (ref "R28") (pin "2") (pintype "passive"))
      (node (ref "U8") (pin "C1") (pinfunction "CH1_OUT+_C1") (pintype "output"))
    )
    (net (code "51") (name "/USB_HOST_D_CM_P") (class "Default")
      (node (ref "R29") (pin "2") (pintype "passive"))
      (node (ref "U8") (pin "C2") (pinfunction "CH1_OUT-_C2") (pintype "output"))
    )
    (net (code "52") (name "/USB_HOST_D_N") (class "Default")
      (node (ref "J3") (pin "2") (pinfunction "D-_2") (pintype "passive"))
      (node (ref "TP50") (pin "1") (pinfunction "1_1") (pintype "passive"))
      (node (ref "U8") (pin "A1") (pinfunction "CH1_IN+_A1") (pintype "input"))
    )
    (net (code "53") (name "/USB_HOST_D_P") (class "Default")
      (node (ref "J3") (pin "3") (pinfunction "D+_3") (pintype "passive"))
      (node (ref "TP51") (pin "1") (pinfunction "1_1") (pintype "passive"))
      (node (ref "U8") (pin "A2") (pinfunction "CH1_IN-_A2") (pintype "input"))
    )
    (net (code "54") (name "/USB_HOST_RX_N") (class "Default")
      (node (ref "J3") (pin "5") (pinfunction "SSRX-_5") (pintype "passive"))
      (node (ref "U8") (pin "A3") (pinfunction "CH2_IN+_A3") (pintype "input"))
    )
    (net (code "55") (name "/USB_HOST_RX_P") (class "Default")
      (node (ref "J3") (pin "6") (pinfunction "SSRX+_6") (pintype "passive"))
      (node (ref "U8") (pin "A4") (pinfunction "CH2_IN-_A4") (pintype "input"))
    )
    (net (code "56") (name "/USB_HOST_TX_CM_N") (class "Default")
      (node (ref "C121") (pin "2") (pinfunction "2_2") (pintype "passive"))
      (node (ref "U8") (pin "C5") (pinfunction "CH3_OUT+_C5") (pintype "output"))
    )
    (net (code "57") (name "/USB_HOST_TX_CM_P") (class "Default")
      (node (ref "C122") (pin "2") (pinfunction "2_2") (pintype "passive"))
      (node (ref "U8") (pin "C6") (pinfunction "CH3_OUT-_C6") (pintype "output"))
    )
    (net (code "58") (name "/USB_HOST_TX_N") (class "Default")
      (node (ref "J3") (pin "8") (pinfunction "SSTX-_8") (pintype "passive"))
      (node (ref "U8") (pin "A5") (pinfunction "CH3_IN+_A5") (pintype "input"))
    )
    (net (code "59") (name "/USB_HOST_TX_P") (class "Default")
      (node (ref "J3") (pin "9") (pinfunction "SSTX+_9") (pintype "passive"))
      (node (ref "U8") (pin "A6") (pinfunction "CH3_IN-_A6") (pintype "input"))
    )
    (net (code "60") (name "/USB_TYPEC_SEL") (class "Default")
      (node (ref "R144") (pin "1") (pintype "passive"))
      (node (ref "R6") (pin "2") (pintype "passive"))
      (node (ref "U5") (pin "16") (pinfunction "SEL_16") (pintype "input"))
      (node (ref "U9") (pin "11") (pinfunction "EXT_SEL_11") (pintype "open_collector"))
    )
    (net (code "61") (name "/USB_VBUS_2") (class "Default")
      (node (ref "C120") (pin "1") (pinfunction "1_1") (pintype "passive"))
      (node (ref "C23") (pin "1") (pinfunction "1_1") (pintype "passive"))
      (node (ref "ESD5") (pin "2") (pinfunction "2_2") (pintype "passive"))
      (node (ref "J3") (pin "1") (pinfunction "VBUS_1") (pintype "power_in"))
      (node (ref "R162") (pin "2") (pintype "passive"))
      (node (ref "TP29") (pin "1") (pinfunction "1_1") (pintype "passive"))
    )
    (net (code "62") (name "/VBUS_CTRL") (class "Default")
      (node (ref "R12") (pin "1") (pintype "passive"))
      (node (ref "R14") (pin "2") (pintype "passive"))
      (node (ref "U14") (pin "A1") (pinfunction "CTRL_A1") (pintype "passive"))
    )
    (net (code "63") (name "/VBUS_DT") (class "Default")
      (node (ref "TP6") (pin "1") (pinfunction "1_1") (pintype "passive"))
      (node (ref "U14") (pin "B1") (pinfunction "VDET_B1") (pintype "passive"))
    )
    (net (code "64") (name "/VIN_CC1") (class "Default")
      (node (ref "ESD17") (pin "2") (pinfunction "2_2") (pintype "passive"))
      (node (ref "J2") (pin "A5") (pinfunction "CC1_A5") (pintype "passive"))
      (node (ref "R33") (pin "2") (pintype "passive"))
    )
    (net (code "65") (name "/VIN_CC2") (class "Default")
      (node (ref "ESD6") (pin "2") (pinfunction "2_2") (pintype "passive"))
      (node (ref "J2") (pin "B5") (pinfunction "CC2_B5") (pintype "passive"))
      (node (ref "R32") (pin "2") (pintype "passive"))
    )
    (net (code "66") (name "BB_1V8") (class "Default")
      (node (ref "C113") (pin "1") (pinfunction "1_1") (pintype "passive"))
      (node (ref "C114") (pin "1") (pinfunction "1_1") (pintype "passive"))
      (node (ref "R10") (pin "1") (pintype "passive"))
      (node (ref "R144") (pin "2") (pintype "passive"))
      (node (ref "R6") (pin "1") (pintype "passive"))
      (node (ref "R7") (pin "1") (pintype "passive"))
      (node (ref "R8") (pin "1") (pintype "passive"))
      (node (ref "R9") (pin "1") (pintype "passive"))
      (node (ref "U5") (pin "5") (pinfunction "VDD1V8_5") (pintype "power_in"))
    )
    (net (code "67") (name "BOOST_5V") (class "Default")
      (node (ref "C21") (pin "1") (pinfunction "1_1") (pintype "passive"))
      (node (ref "C22") (pin "1") (pinfunction "1_1") (pintype "passive"))
      (node (ref "C90") (pin "1") (pinfunction "1_1") (pintype "passive"))
      (node (ref "TP28") (pin "1") (pinfunction "1_1") (pintype "passive"))
      (node (ref "U6") (pin "B1") (pinfunction "VINT1_B1") (pintype "input"))
      (node (ref "U6") (pin "B2") (pinfunction "VINT2_B2") (pintype "input"))
      (node (ref "U6") (pin "C1") (pinfunction "VINT3_C1") (pintype "input"))
      (node (ref "U7") (pin "A1") (pinfunction "VOUT_A1") (pintype "power_in"))
      (node (ref "U7") (pin "A2") (pinfunction "VOUT_A2") (pintype "power_in"))
    )
    (net (code "68") (name "DCDC_5V") (class "Default")
      (node (ref "C33") (pin "1") (pinfunction "1_1") (pintype "passive"))
      (node (ref "C42") (pin "1") (pinfunction "1_1") (pintype "passive"))
      (node (ref "C43") (pin "1") (pinfunction "1_1") (pintype "passive"))
      (node (ref "C95") (pin "1") (pinfunction "1_1") (pintype "passive"))
      (node (ref "L9") (pin "1") (pinfunction "1_1") (pintype "passive"))
      (node (ref "R25") (pin "2") (pintype "passive"))
      (node (ref "TP8") (pin "1") (pinfunction "1_1") (pintype "passive"))
      (node (ref "U14") (pin "A2") (pinfunction "OUT_A2") (pintype "passive"))
      (node (ref "U14") (pin "A3") (pinfunction "OUT_A3") (pintype "passive"))
      (node (ref "U14") (pin "B2") (pinfunction "OUT_B2") (pintype "passive"))
      (node (ref "U7") (pin "A3") (pinfunction "VIN_A3") (pintype "power_in"))
    )
    (net (code "69") (name "GND") (class "Default")
      (node (ref "C101") (pin "2") (pinfunction "2_2") (pintype "passive"))
      (node (ref "C102") (pin "2") (pinfunction "2_2") (pintype "passive"))
      (node (ref "C113") (pin "2") (pinfunction "2_2") (pintype "passive"))
      (node (ref "C114") (pin "2") (pinfunction "2_2") (pintype "passive"))
      (node (ref "C120") (pin "2") (pinfunction "2_2") (pintype "passive"))
      (node (ref "C16") (pin "2") (pinfunction "2_2") (pintype "passive"))
      (node (ref "C17") (pin "2") (pinfunction "2_2") (pintype "passive"))
      (node (ref "C21") (pin "2") (pinfunction "2_2") (pintype "passive"))
      (node (ref "C22") (pin "2") (pinfunction "2_2") (pintype "passive"))
      (node (ref "C23") (pin "2") (pinfunction "2_2") (pintype "passive"))
      (node (ref "C33") (pin "2") (pinfunction "2_2") (pintype "passive"))
      (node (ref "C42") (pin "2") (pinfunction "2_2") (pintype "passive"))
      (node (ref "C43") (pin "2") (pinfunction "2_2") (pintype "passive"))
      (node (ref "C46") (pin "2") (pinfunction "2_2") (pintype "passive"))
      (node (ref "C47") (pin "2") (pinfunction "2_2") (pintype "passive"))
      (node (ref "C48") (pin "2") (pinfunction "2_2") (pintype "passive"))
      (node (ref "C49") (pin "2") (pinfunction "2_2") (pintype "passive"))
      (node (ref "C50") (pin "2") (pinfunction "2_2") (pintype "passive"))
      (node (ref "C90") (pin "2") (pinfunction "2_2") (pintype "passive"))
      (node (ref "C95") (pin "2") (pinfunction "2_2") (pintype "passive"))
      (node (ref "ESD1") (pin "1") (pinfunction "1_1") (pintype "passive"))
      (node (ref "ESD17") (pin "1") (pinfunction "1_1") (pintype "passive"))
      (node (ref "ESD2") (pin "1") (pinfunction "1_1") (pintype "passive"))
      (node (ref "ESD3") (pin "1") (pinfunction "1_1") (pintype "passive"))
      (node (ref "ESD4") (pin "1") (pinfunction "1_1") (pintype "passive"))
      (node (ref "ESD5") (pin "1") (pinfunction "1_1") (pintype "passive"))
      (node (ref "ESD6") (pin "1") (pinfunction "1_1") (pintype "passive"))
      (node (ref "J1") (pin "A1") (pinfunction "GND#A1_A1") (pintype "passive"))
      (node (ref "J1") (pin "A12") (pinfunction "GND#A12_A12") (pintype "passive"))
      (node (ref "J1") (pin "B1") (pinfunction "GND#B1_B1") (pintype "passive"))
      (node (ref "J1") (pin "B12") (pinfunction "GND#B12_B12") (pintype "passive"))
      (node (ref "J1") (pin "SH1") (pinfunction "TAB#T1_SH1") (pintype "passive"))
      (node (ref "J1") (pin "SH2") (pinfunction "TAB#T2_SH2") (pintype "passive"))
      (node (ref "J1") (pin "SH3") (pinfunction "TAB#T3_SH3") (pintype "passive"))
      (node (ref "J1") (pin "SH4") (pinfunction "TAB#T4_SH4") (pintype "passive"))
      (node (ref "J2") (pin "A1") (pinfunction "GND#A1_A1") (pintype "passive"))
      (node (ref "J2") (pin "A12") (pinfunction "GND#A12_A12") (pintype "passive"))
      (node (ref "J2") (pin "B1") (pinfunction "GND#B1_B1") (pintype "passive"))
      (node (ref "J2") (pin "B12") (pinfunction "GND#B12_B12") (pintype "passive"))
      (node (ref "J2") (pin "SH1") (pinfunction "TAB#T1_SH1") (pintype "passive"))
      (node (ref "J2") (pin "SH2") (pinfunction "TAB#T2_SH2") (pintype "passive"))
      (node (ref "J2") (pin "SH3") (pinfunction "TAB#T3_SH3") (pintype "passive"))
      (node (ref "J2") (pin "SH4") (pinfunction "TAB#T4_SH4") (pintype "passive"))
      (node (ref "J3") (pin "10") (pinfunction "G1_10") (pintype "power_in"))
      (node (ref "J3") (pin "11") (pinfunction "G2_11") (pintype "power_in"))
      (node (ref "J3") (pin "12") (pinfunction "G3_12") (pintype "power_in"))
      (node (ref "J3") (pin "13") (pinfunction "G4_13") (pintype "power_in"))
      (node (ref "J3") (pin "4") (pinfunction "GND_4") (pintype "power_in"))
      (node (ref "J3") (pin "7") (pinfunction "GND_DRAIN_7") (pintype "power_in"))
      (node (ref "Q3") (pin "2") (pinfunction "SOURCE_2") (pintype "passive"))
      (node (ref "R12") (pin "2") (pintype "passive"))
      (node (ref "R19") (pin "1") (pintype "passive"))
      (node (ref "R22") (pin "1") (pintype "passive"))
      (node (ref "R31") (pin "1") (pintype "passive"))
      (node (ref "R32") (pin "1") (pintype "passive"))
      (node (ref "R33") (pin "1") (pintype "passive"))
      (node (ref "R98") (pin "2") (pintype "passive"))
      (node (ref "TP36") (pin "1") (pinfunction "1_1") (pintype "passive"))
      (node (ref "TP37") (pin "1") (pinfunction "1_1") (pintype "passive"))
      (node (ref "TP41") (pin "1") (pinfunction "1_1") (pintype "passive"))
      (node (ref "TP42") (pin "1") (pinfunction "1_1") (pintype "passive"))
      (node (ref "TP43") (pin "1") (pinfunction "1_1") (pintype "passive"))
      (node (ref "TP44") (pin "1") (pinfunction "1_1") (pintype "passive"))
      (node (ref "U13") (pin "B3") (pinfunction "GND1_B3") (pintype "power_in"))
      (node (ref "U13") (pin "C3") (pinfunction "GND2_C3") (pintype "power_in"))
      (node (ref "U13") (pin "D3") (pinfunction "GND3_D3") (pintype "power_in"))
      (node (ref "U14") (pin "A4") (pinfunction "GND_A4") (pintype "passive"))
      (node (ref "U14") (pin "B4") (pinfunction "GND_B4") (pintype "passive"))
      (node (ref "U14") (pin "C1") (pinfunction "OVLO_C1") (pintype "passive"))
      (node (ref "U14") (pin "C4") (pinfunction "GND_C4") (pintype "passive"))
      (node (ref "U16") (pin "B1") (pinfunction "GND_CH1_B1") (pintype "power_in"))
      (node (ref "U16") (pin "B2") (pinfunction "GND_CH2_B2") (pintype "power_in"))
      (node (ref "U16") (pin "B3") (pinfunction "GND_CH3_B3") (pintype "power_in"))
      (node (ref "U17") (pin "B1") (pinfunction "GND_CH1_B1") (pintype "power_in"))
      (node (ref "U17") (pin "B2") (pinfunction "GND_CH2_B2") (pintype "power_in"))
      (node (ref "U5") (pin "19") (pinfunction "GND_19") (pintype "power_in"))
      (node (ref "U6") (pin "B3") (pinfunction "GND1_B3") (pintype "power_in"))
      (node (ref "U6") (pin "C3") (pinfunction "GND2_C3") (pintype "power_in"))
      (node (ref "U6") (pin "D3") (pinfunction "GND3_D3") (pintype "power_in"))
      (node (ref "U7") (pin "C1") (pinfunction "GND_C1") (pintype "power_in"))
      (node (ref "U7") (pin "C2") (pinfunction "GND_C2") (pintype "power_in"))
      (node (ref "U8") (pin "B1") (pinfunction "GND_CH1_B1") (pintype "power_in"))
      (node (ref "U8") (pin "B2") (pinfunction "GND_CH2_B2") (pintype "power_in"))
      (node (ref "U8") (pin "B3") (pinfunction "GND_CH3_B3") (pintype "power_in"))
      (node (ref "U9") (pin "10") (pinfunction "GND_10") (pintype "power_in"))
    )
    (net (code "70") (name "Net-(L9-Pad2)") (class "Default")
      (node (ref "L9") (pin "2") (pinfunction "2_2") (pintype "passive"))
      (node (ref "U7") (pin "B1") (pinfunction "SW_B1") (pintype "power_in"))
      (node (ref "U7") (pin "B2") (pinfunction "SW_B2") (pintype "power_in"))
    )
    (net (code "71") (name "Net-(Q3-DRAIN)") (class "Default")
      (node (ref "Q3") (pin "3") (pinfunction "DRAIN_3") (pintype "passive"))
      (node (ref "R30") (pin "1") (pintype "passive"))
      (node (ref "U13") (pin "A1") (pinfunction "EN_A1") (pintype "input"))
    )
    (net (code "72") (name "Net-(U5-CH1_SET1{slash}RXDE)") (class "Default")
      (node (ref "R7") (pin "2") (pintype "passive"))
      (node (ref "U5") (pin "1") (pinfunction "CH1_SET1/RXDE_1") (pintype "input"))
    )
    (net (code "73") (name "Net-(U5-CH1_SET2{slash}TXEQ)") (class "Default")
      (node (ref "R8") (pin "2") (pintype "passive"))
      (node (ref "U5") (pin "4") (pinfunction "CH1_SET2/TXEQ_4") (pintype "input"))
    )
    (net (code "74") (name "Net-(U5-CH2_SET1{slash}TXDE)") (class "Default")
      (node (ref "R9") (pin "2") (pintype "passive"))
      (node (ref "U5") (pin "13") (pinfunction "CH2_SET1/TXDE_13") (pintype "input"))
    )
    (net (code "75") (name "Net-(U5-CH2_SET2{slash}RXEQ)") (class "Default")
      (node (ref "R10") (pin "2") (pintype "passive"))
      (node (ref "U5") (pin "10") (pinfunction "CH2_SET2/RXEQ_10") (pintype "input"))
    )
    (net (code "76") (name "Net-(U6-EN)") (class "Default")
      (node (ref "D1") (pin "A") (pinfunction "A_A") (pintype "passive"))
      (node (ref "R21") (pin "1") (pintype "passive"))
      (node (ref "U6") (pin "A1") (pinfunction "EN_A1") (pintype "input"))
    )
    (net (code "77") (name "Net-(U6-ILIM)") (class "Default")
      (node (ref "R19") (pin "2") (pintype "passive"))
      (node (ref "U6") (pin "A3") (pinfunction "ILIM_A3") (pintype "passive"))
    )
    (net (code "78") (name "Net-(U6-VBUS1)") (class "Default")
      (node (ref "R162") (pin "1") (pintype "passive"))
      (node (ref "U6") (pin "C2") (pinfunction "VBUS1_C2") (pintype "passive"))
      (node (ref "U6") (pin "D1") (pinfunction "VBUS2_D1") (pintype "passive"))
      (node (ref "U6") (pin "D2") (pinfunction "VBUS3_D2") (pintype "passive"))
    )
    (net (code "79") (name "Net-(U6-~{FAULT})") (class "Default")
      (node (ref "D1") (pin "K") (pinfunction "K_K") (pintype "passive"))
      (node (ref "U6") (pin "A2") (pinfunction "~{FAULT}_A2") (pintype "open_collector"))
    )
    (net (code "80") (name "Net-(U7-EN)") (class "Default")
      (node (ref "R161") (pin "1") (pintype "passive"))
      (node (ref "U7") (pin "B3") (pinfunction "EN_B3") (pintype "input"))
    )
    (net (code "81") (name "Net-(U7-MODE)") (class "Default")
      (node (ref "R98") (pin "1") (pintype "passive"))
      (node (ref "U7") (pin "C3") (pinfunction "MODE_C3") (pintype "input"))
    )
    (net (code "82") (name "Net-(U9-PORT)") (class "Default")
      (node (ref "R2") (pin "1") (pintype "passive"))
      (node (ref "R22") (pin "2") (pintype "passive"))
      (node (ref "U9") (pin "3") (pinfunction "PORT_3") (pintype "input"))
    )
    (net (code "83") (name "Net-(U13-ILIM)") (class "Default")
      (node (ref "R31") (pin "2") (pintype "passive"))
      (node (ref "U13") (pin "A3") (pinfunction "ILIM_A3") (pintype "passive"))
    )
    (net (code "84") (name "Net-(U13-~{FAULT})") (class "Default")
      (node (ref "R27") (pin "1") (pintype "passive"))
      (node (ref "U13") (pin "A2") (pinfunction "~{FAULT}_A2") (pintype "open_collector"))
    )
    (net (code "85") (name "USB_VBUS_1") (class "Default")
      (node (ref "C101") (pin "1") (pinfunction "1_1") (pintype "passive"))
      (node (ref "C102") (pin "1") (pinfunction "1_1") (pintype "passive"))
      (node (ref "C17") (pin "1") (pinfunction "1_1") (pintype "passive"))
      (node (ref "D5") (pin "A") (pinfunction "A_A") (pintype "passive"))
      (node (ref "J1") (pin "A4") (pinfunction "VBUS#A4_A4") (pintype "passive"))
      (node (ref "J1") (pin "A9") (pinfunction "VBUS#A9_A9") (pintype "passive"))
      (node (ref "J1") (pin "B4") (pinfunction "VBUS#B4_B4") (pintype "passive"))
      (node (ref "J1") (pin "B9") (pinfunction "VBUS#B9_B9") (pintype "passive"))
      (node (ref "R1") (pin "2") (pintype "passive"))
      (node (ref "R176") (pin "1") (pintype "passive"))
      (node (ref "TP22") (pin "1") (pinfunction "1_1") (pintype "passive"))
      (node (ref "TP38") (pin "1") (pinfunction "1_1") (pintype "passive"))
      (node (ref "U13") (pin "C2") (pinfunction "VBUS1_C2") (pintype "passive"))
      (node (ref "U13") (pin "D1") (pinfunction "VBUS2_D1") (pintype "passive"))
      (node (ref "U13") (pin "D2") (pinfunction "VBUS3_D2") (pintype "passive"))
      (node (ref "U9") (pin "4") (pinfunction "VBUS_DET_4") (pintype "input"))
    )
    (net (code "86") (name "USB_VIN") (class "Default")
      (node (ref "C49") (pin "1") (pinfunction "1_1") (pintype "passive"))
      (node (ref "C50") (pin "1") (pinfunction "1_1") (pintype "passive"))
      (node (ref "D12") (pin "A") (pinfunction "A_A") (pintype "passive"))
      (node (ref "J2") (pin "A4") (pinfunction "VBUS#A4_A4") (pintype "passive"))
      (node (ref "J2") (pin "A9") (pinfunction "VBUS#A9_A9") (pintype "passive"))
      (node (ref "J2") (pin "B4") (pinfunction "VBUS#B4_B4") (pintype "passive"))
      (node (ref "J2") (pin "B9") (pinfunction "VBUS#B9_B9") (pintype "passive"))
      (node (ref "R26") (pin "1") (pintype "passive"))
      (node (ref "TP27") (pin "1") (pinfunction "1_1") (pintype "passive"))
      (node (ref "TP39") (pin "1") (pinfunction "1_1") (pintype "passive"))
      (node (ref "TP40") (pin "1") (pinfunction "1_1") (pintype "passive"))
      (node (ref "U13") (pin "B1") (pinfunction "VINT1_B1") (pintype "input"))
      (node (ref "U13") (pin "B2") (pinfunction "VINT2_B2") (pintype "input"))
      (node (ref "U13") (pin "C1") (pinfunction "VINT3_C1") (pintype "input"))
    )
    (net (code "87") (name "V3V3") (class "Default")
      (node (ref "C16") (pin "1") (pinfunction "1_1") (pintype "passive"))
      (node (ref "R11") (pin "2") (pintype "passive"))
      (node (ref "R161") (pin "2") (pintype "passive"))
      (node (ref "R2") (pin "2") (pintype "passive"))
      (node (ref "R21") (pin "2") (pintype "passive"))
      (node (ref "R27") (pin "2") (pintype "passive"))
      (node (ref "R3") (pin "2") (pintype "passive"))
      (node (ref "R30") (pin "2") (pintype "passive"))
      (node (ref "R4") (pin "2") (pintype "passive"))
      (node (ref "U9") (pin "12") (pinfunction "VDD_12") (pintype "power_in"))
    )
    (net (code "88") (name "VSYS") (class "Default")
      (node (ref "C46") (pin "1") (pinfunction "1_1") (pintype "passive"))
      (node (ref "C47") (pin "1") (pinfunction "1_1") (pintype "passive"))
      (node (ref "C48") (pin "1") (pinfunction "1_1") (pintype "passive"))
      (node (ref "D12") (pin "C") (pinfunction "C_C") (pintype "passive"))
      (node (ref "D5") (pin "C") (pinfunction "C_C") (pintype "passive"))
      (node (ref "R176") (pin "2") (pintype "passive"))
      (node (ref "R26") (pin "2") (pintype "passive"))
      (node (ref "TP7") (pin "1") (pinfunction "1_1") (pintype "passive"))
      (node (ref "U14") (pin "B3") (pinfunction "IN_B3") (pintype "passive"))
      (node (ref "U14") (pin "C2") (pinfunction "IN_C2") (pintype "passive"))
      (node (ref "U14") (pin "C3") (pinfunction "IN_C3") (pintype "passive"))
    )
    (net (code "89") (name "unconnected-(J2-DN1-PadA7)") (class "Default")
      (node (ref "J2") (pin "A7") (pinfunction "DN1_A7") (pintype "passive"))
    )
    (net (code "90") (name "unconnected-(J2-DN2-PadB7)") (class "Default")
      (node (ref "J2") (pin "B7") (pinfunction "DN2_B7") (pintype "passive"))
    )
    (net (code "91") (name "unconnected-(J2-DP1-PadA6)") (class "Default")
      (node (ref "J2") (pin "A6") (pinfunction "DP1_A6") (pintype "passive"))
    )
    (net (code "92") (name "unconnected-(J2-DP2-PadB6)") (class "Default")
      (node (ref "J2") (pin "B6") (pinfunction "DP2_B6") (pintype "passive"))
    )
    (net (code "93") (name "unconnected-(J2-SSRX1N-PadB10)") (class "Default")
      (node (ref "J2") (pin "B10") (pinfunction "SSRX1N_B10") (pintype "passive"))
    )
    (net (code "94") (name "unconnected-(J2-SSRX1P-PadB11)") (class "Default")
      (node (ref "J2") (pin "B11") (pinfunction "SSRX1P_B11") (pintype "passive"))
    )
    (net (code "95") (name "unconnected-(J2-SSRX2N-PadA10)") (class "Default")
      (node (ref "J2") (pin "A10") (pinfunction "SSRX2N_A10") (pintype "passive"))
    )
    (net (code "96") (name "unconnected-(J2-SSRX2P-PadA11)") (class "Default")
      (node (ref "J2") (pin "A11") (pinfunction "SSRX2P_A11") (pintype "passive"))
    )
    (net (code "97") (name "unconnected-(J2-SSTX1N-PadA3)") (class "Default")
      (node (ref "J2") (pin "A3") (pinfunction "SSTX1N_A3") (pintype "passive"))
    )
    (net (code "98") (name "unconnected-(J2-SSTX1P-PadA2)") (class "Default")
      (node (ref "J2") (pin "A2") (pinfunction "SSTX1P_A2") (pintype "passive"))
    )
    (net (code "99") (name "unconnected-(J2-SSTX2N-PadB3)") (class "Default")
      (node (ref "J2") (pin "B3") (pinfunction "SSTX2N_B3") (pintype "passive"))
    )
    (net (code "100") (name "unconnected-(J2-SSTX2P-PadB2)") (class "Default")
      (node (ref "J2") (pin "B2") (pinfunction "SSTX2P_B2") (pintype "passive"))
    )
    (net (code "101") (name "unconnected-(J2-SUB1-PadA8)") (class "Default")
      (node (ref "J2") (pin "A8") (pinfunction "SUB1_A8") (pintype "passive"))
    )
    (net (code "102") (name "unconnected-(J2-SUB2-PadB8)") (class "Default")
      (node (ref "J2") (pin "B8") (pinfunction "SUB2_B8") (pintype "passive"))
    )
    (net (code "103") (name "unconnected-(R14-Pad1)") (class "Default")
      (node (ref "R14") (pin "1") (pintype "passive+no_connect"))
    )
  )
)
